# USBBreakout-2_0.net
KiCad netlist of a schematic drawn in EAGLE
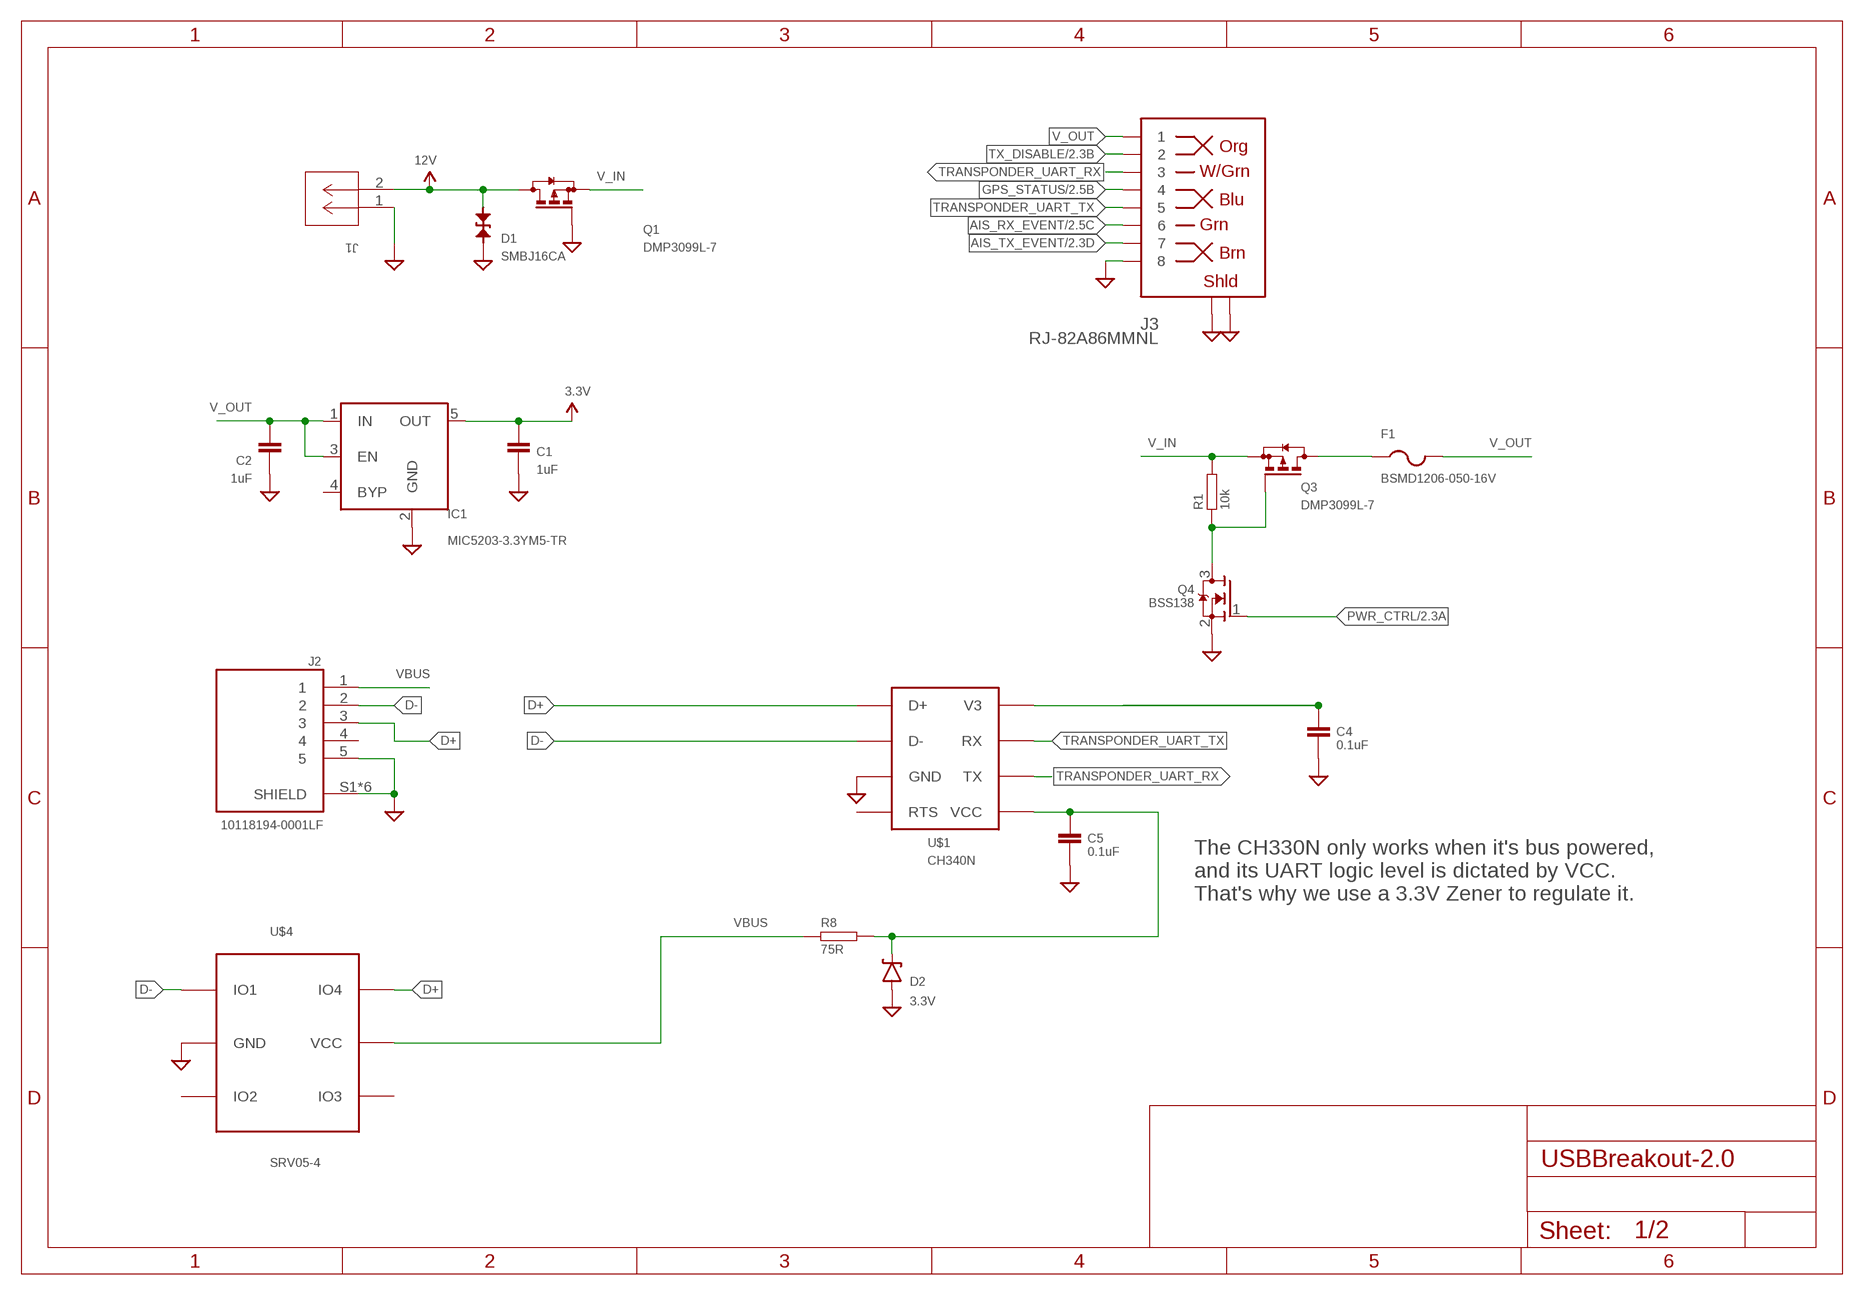
[diagram p0: schematic, sheet 1]
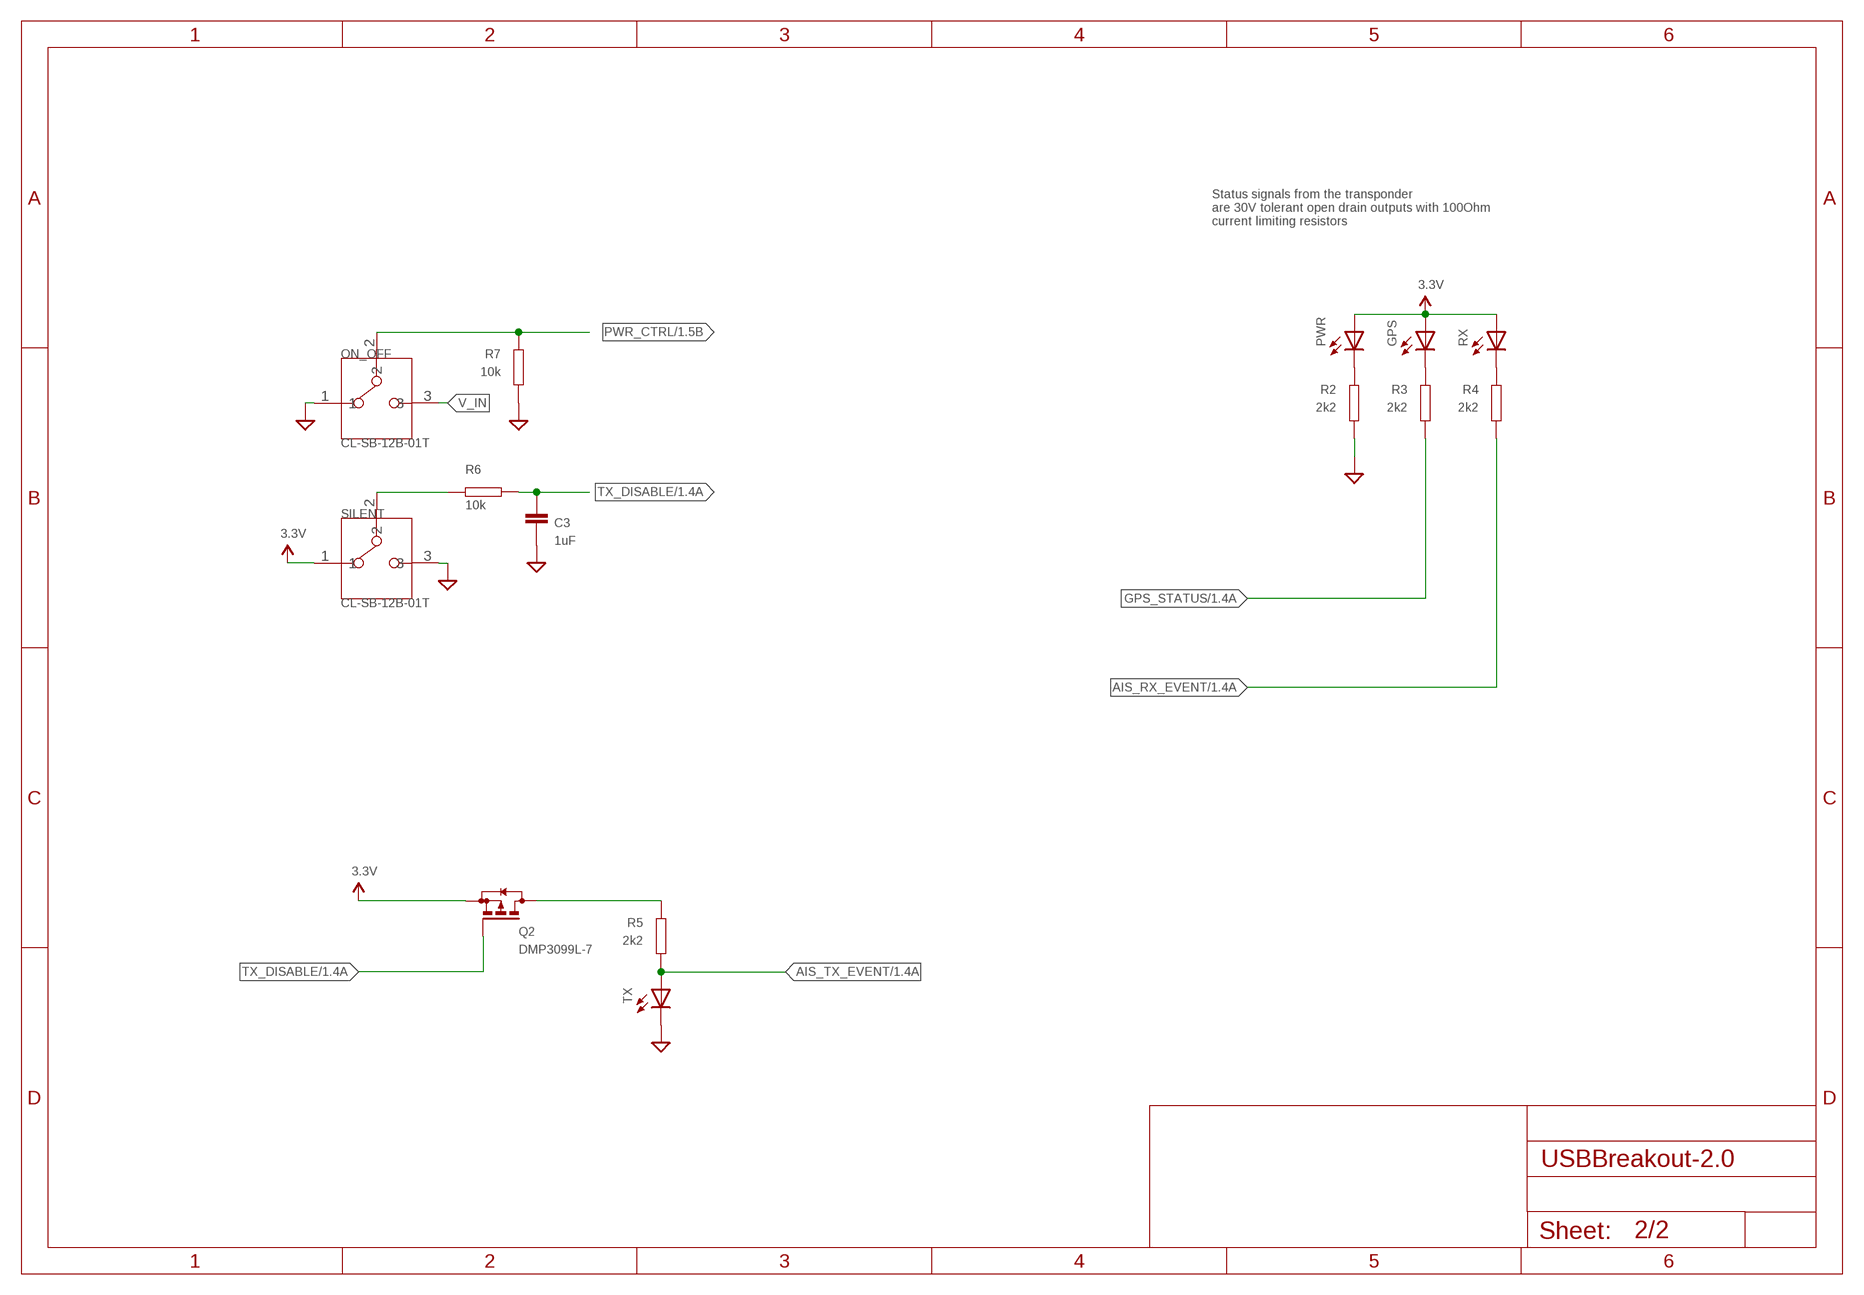
[diagram p1: schematic, sheet 2]

(export (version "E")
  (design (tool "Eeschema 10.0.6"))
  (components
    (comp (ref "C1")
      (value "1uF")
      (footprint "eagle-import:0603")
      (libsource (lib "eagle-import") (part "CAPACITOR0603"))
    )
    (comp (ref "C2")
      (value "1uF")
      (footprint "eagle-import:0603")
      (libsource (lib "eagle-import") (part "CAPACITOR0603"))
    )
    (comp (ref "C4")
      (value "0.1uF")
      (footprint "eagle-import:0603")
      (libsource (lib "eagle-import") (part "CAPACITOR0603"))
    )
    (comp (ref "C5")
      (value "0.1uF")
      (footprint "eagle-import:0603")
      (libsource (lib "eagle-import") (part "CAPACITOR0603"))
    )
    (comp (ref "D1")
      (value "SMBJ16CA")
      (footprint "eagle-import:SMB-BIDIR")
      (libsource (lib "eagle-import") (part "DIODE-TVS-BIDIRSMB"))
    )
    (comp (ref "D2")
      (value "3.3V")
      (footprint "eagle-import:SOD-323")
      (libsource (lib "eagle-import") (part "DIODE-ZENER3.3V"))
    )
    (comp (ref "F1")
      (value "BSMD1206-050-16V")
      (footprint "eagle-import:R1206")
      (libsource (lib "eagle-import") (part "PTCFUSE-1206"))
    )
    (comp (ref "IC1")
      (value "MIC5203-3.3YM5-TR")
      (footprint "eagle-import:SOT23-5")
      (libsource (lib "eagle-import") (part "MIC5219XX"))
    )
    (comp (ref "J1")
      (value "OSTVN02A150")
      (footprint "eagle-import:CONN_OSTVN02A150_OST")
      (fields (field (name "COPYRIGHT") "Copyright (C) 2018 Accelerated Designs. All rights reserved"))
      (libsource (lib "eagle-import") (part "OSTVN02A150"))
    )
    (comp (ref "J2")
      (value "10118194-0001LF")
      (footprint "eagle-import:AMPHENOL_10118194-0001LF")
      (fields (field (name "MF") "Amphenol ICC (FCI)"))
      (libsource (lib "eagle-import") (part "10118194-0001LF"))
    )
    (comp (ref "J3")
      (value "RJ-82A86MMNL")
      (footprint "eagle-import:RJ-82A86MMNL")
      (libsource (lib "eagle-import") (part "RJ-82A86MMNL"))
    )
    (comp (ref "Q1")
      (value "DMP3099L-7")
      (footprint "eagle-import:SOT23")
      (libsource (lib "eagle-import") (part "BSS84"))
    )
    (comp (ref "Q3")
      (value "DMP3099L-7")
      (footprint "eagle-import:SOT23")
      (libsource (lib "eagle-import") (part "BSS84"))
    )
    (comp (ref "Q4")
      (value "BSS138")
      (footprint "eagle-import:SOT23")
      (libsource (lib "eagle-import") (part "MOSFET-NREFLOW"))
    )
    (comp (ref "R1")
      (value "10k")
      (footprint "eagle-import:0603")
      (libsource (lib "eagle-import") (part "RESISTOR0603"))
    )
    (comp (ref "R8")
      (value "75R")
      (footprint "eagle-import:0603")
      (libsource (lib "eagle-import") (part "RESISTOR0603"))
    )
    (comp (ref "U$1")
      (value "CH340N")
      (footprint "eagle-import:SOIC-8")
      (libsource (lib "eagle-import") (part "CH330N"))
    )
    (comp (ref "U$4")
      (value "SRV05-4")
      (footprint "eagle-import:SOT23-6")
      (libsource (lib "eagle-import") (part "SRV05-4"))
    )
    (comp (ref "C3")
      (value "1uF")
      (footprint "eagle-import:0603")
      (libsource (lib "eagle-import") (part "CAPACITOR0603"))
    )
    (comp (ref "GPS")
      (value "LEDCHIPLED_1206")
      (footprint "eagle-import:CHIPLED_1206")
      (fields (field (name "PARTNO") "TJ-S3216CL9T5ALC2G-A5"))
      (libsource (lib "eagle-import") (part "LEDCHIPLED_1206"))
    )
    (comp (ref "ON_OFF")
      (value "CL-SB-12B-01T")
      (footprint "eagle-import:CL-SB-12B")
      (fields (field (name "MF") "Nidec Copal"))
      (libsource (lib "eagle-import") (part "CL-SB-12B-01T"))
    )
    (comp (ref "PWR")
      (value "LEDCHIPLED_1206")
      (footprint "eagle-import:CHIPLED_1206")
      (fields (field (name "PARTNO") "TJ-S3216CL9T5ALC2G-A5"))
      (libsource (lib "eagle-import") (part "LEDCHIPLED_1206"))
    )
    (comp (ref "Q2")
      (value "DMP3099L-7")
      (footprint "eagle-import:SOT23")
      (libsource (lib "eagle-import") (part "BSS84"))
    )
    (comp (ref "R2")
      (value "2k2")
      (footprint "eagle-import:0603")
      (libsource (lib "eagle-import") (part "RESISTOR0603"))
    )
    (comp (ref "R3")
      (value "2k2")
      (footprint "eagle-import:0603")
      (libsource (lib "eagle-import") (part "RESISTOR0603"))
    )
    (comp (ref "R4")
      (value "2k2")
      (footprint "eagle-import:0603")
      (libsource (lib "eagle-import") (part "RESISTOR0603"))
    )
    (comp (ref "R5")
      (value "2k2")
      (footprint "eagle-import:0603")
      (libsource (lib "eagle-import") (part "RESISTOR0603"))
    )
    (comp (ref "R6")
      (value "10k")
      (footprint "eagle-import:0603")
      (libsource (lib "eagle-import") (part "RESISTOR0603"))
    )
    (comp (ref "R7")
      (value "10k")
      (footprint "eagle-import:0603")
      (libsource (lib "eagle-import") (part "RESISTOR0603"))
    )
    (comp (ref "RX")
      (value "LEDCHIPLED_1206")
      (footprint "eagle-import:CHIPLED_1206")
      (fields (field (name "PARTNO") "TJ-S3216CL9T5ALC2G-A5"))
      (libsource (lib "eagle-import") (part "LEDCHIPLED_1206"))
    )
    (comp (ref "SILENT")
      (value "CL-SB-12B-01T")
      (footprint "eagle-import:CL-SB-12B")
      (fields (field (name "MF") "Nidec Copal"))
      (libsource (lib "eagle-import") (part "CL-SB-12B-01T"))
    )
    (comp (ref "TX")
      (value "LEDCHIPLED_1206")
      (footprint "eagle-import:CHIPLED_1206")
      (fields (field (name "PARTNO") "TJ-S3216CL9T5ALC2G-A5"))
      (libsource (lib "eagle-import") (part "LEDCHIPLED_1206"))
    )
  )
  (nets
    (net (code "1") (name "3.3V") (class "Default")
      (node (ref "C1") (pin "P$1") (pinfunction "1_P$1") (pintype "passive"))
      (node (ref "GPS") (pin "A") (pinfunction "A_A") (pintype "passive"))
      (node (ref "IC1") (pin "5") (pinfunction "OUT_5") (pintype "output"))
      (node (ref "PWR") (pin "A") (pinfunction "A_A") (pintype "passive"))
      (node (ref "Q2") (pin "2") (pinfunction "S_2") (pintype "passive"))
      (node (ref "RX") (pin "A") (pinfunction "A_A") (pintype "passive"))
      (node (ref "SILENT") (pin "1") (pinfunction "1_1") (pintype "bidirectional"))
    )
    (net (code "2") (name "12V") (class "Default")
      (node (ref "D1") (pin "A") (pinfunction "P$1_A") (pintype "bidirectional"))
      (node (ref "J1") (pin "2") (pinfunction "2_2") (pintype "passive"))
      (node (ref "Q1") (pin "3") (pinfunction "D_3") (pintype "passive"))
    )
    (net (code "3") (name "AIS_RX_EVENT") (class "Default")
      (node (ref "J3") (pin "P$6") (pinfunction "6_P$6") (pintype "bidirectional"))
      (node (ref "R4") (pin "P$2") (pinfunction "P$2_P$2") (pintype "passive"))
    )
    (net (code "4") (name "AIS_TX_EVENT") (class "Default")
      (node (ref "J3") (pin "P$7") (pinfunction "7_P$7") (pintype "bidirectional"))
      (node (ref "R5") (pin "P$2") (pinfunction "P$2_P$2") (pintype "passive"))
      (node (ref "TX") (pin "A") (pinfunction "A_A") (pintype "passive"))
    )
    (net (code "5") (name "D+") (class "Default")
      (node (ref "J2") (pin "3") (pinfunction "3_3") (pintype "passive"))
      (node (ref "U$1") (pin "1") (pinfunction "D+_1") (pintype "bidirectional"))
      (node (ref "U$4") (pin "6") (pinfunction "IO4_6") (pintype "bidirectional"))
    )
    (net (code "6") (name "D-") (class "Default")
      (node (ref "J2") (pin "2") (pinfunction "2_2") (pintype "passive"))
      (node (ref "U$1") (pin "2") (pinfunction "D-_2") (pintype "bidirectional"))
      (node (ref "U$4") (pin "1") (pinfunction "IO1_1") (pintype "bidirectional"))
    )
    (net (code "7") (name "GND") (class "Default")
      (node (ref "C1") (pin "P$2") (pinfunction "2_P$2") (pintype "passive"))
      (node (ref "C2") (pin "P$2") (pinfunction "2_P$2") (pintype "passive"))
      (node (ref "C3") (pin "P$2") (pinfunction "2_P$2") (pintype "passive"))
      (node (ref "C4") (pin "P$2") (pinfunction "2_P$2") (pintype "passive"))
      (node (ref "C5") (pin "P$2") (pinfunction "2_P$2") (pintype "passive"))
      (node (ref "D1") (pin "C") (pinfunction "P$2_C") (pintype "bidirectional"))
      (node (ref "D2") (pin "A") (pinfunction "A_A") (pintype "passive"))
      (node (ref "IC1") (pin "2") (pinfunction "GND_2") (pintype "power_in"))
      (node (ref "J1") (pin "1") (pinfunction "1_1") (pintype "passive"))
      (node (ref "J2") (pin "5") (pinfunction "5_5") (pintype "passive"))
      (node (ref "J2") (pin "S1") (pinfunction "SHIELD_S1") (pintype "passive"))
      (node (ref "J2") (pin "S2") (pinfunction "SHIELD_S2") (pintype "passive"))
      (node (ref "J2") (pin "S3") (pinfunction "SHIELD_S3") (pintype "passive"))
      (node (ref "J2") (pin "S4") (pinfunction "SHIELD_S4") (pintype "passive"))
      (node (ref "J2") (pin "S5") (pinfunction "SHIELD_S5") (pintype "passive"))
      (node (ref "J2") (pin "S6") (pinfunction "SHIELD_S6") (pintype "passive"))
      (node (ref "J3") (pin "P$10") (pinfunction "SHLD_P$10") (pintype "bidirectional"))
      (node (ref "J3") (pin "P$11") (pinfunction "SHLD_P$11") (pintype "bidirectional"))
      (node (ref "J3") (pin "P$12") (pinfunction "SHLD_P$12") (pintype "bidirectional"))
      (node (ref "J3") (pin "P$8") (pinfunction "8_P$8") (pintype "bidirectional"))
      (node (ref "J3") (pin "P$9") (pinfunction "SHLD_P$9") (pintype "bidirectional"))
      (node (ref "ON_OFF") (pin "1") (pinfunction "1_1") (pintype "bidirectional"))
      (node (ref "Q1") (pin "1") (pinfunction "G_1") (pintype "passive"))
      (node (ref "Q4") (pin "2") (pinfunction "S_2") (pintype "bidirectional"))
      (node (ref "R2") (pin "P$2") (pinfunction "P$2_P$2") (pintype "passive"))
      (node (ref "R7") (pin "P$2") (pinfunction "P$2_P$2") (pintype "passive"))
      (node (ref "SILENT") (pin "3") (pinfunction "3_3") (pintype "bidirectional"))
      (node (ref "TX") (pin "C") (pinfunction "C_C") (pintype "passive"))
      (node (ref "U$1") (pin "3") (pinfunction "GND_3") (pintype "bidirectional"))
      (node (ref "U$4") (pin "2") (pinfunction "GND_2") (pintype "bidirectional"))
    )
    (net (code "8") (name "GPS_STATUS") (class "Default")
      (node (ref "J3") (pin "P$4") (pinfunction "4_P$4") (pintype "bidirectional"))
      (node (ref "R3") (pin "P$2") (pinfunction "P$2_P$2") (pintype "passive"))
    )
    (net (code "9") (name "Net-(C4-1)") (class "Default")
      (node (ref "C4") (pin "P$1") (pinfunction "1_P$1") (pintype "passive"))
      (node (ref "U$1") (pin "8") (pinfunction "V3_8") (pintype "bidirectional"))
    )
    (net (code "10") (name "Net-(C5-1)") (class "Default")
      (node (ref "C5") (pin "P$1") (pinfunction "1_P$1") (pintype "passive"))
      (node (ref "D2") (pin "C") (pinfunction "C_C") (pintype "passive"))
      (node (ref "R8") (pin "P$2") (pinfunction "P$2_P$2") (pintype "passive"))
      (node (ref "U$1") (pin "5") (pinfunction "VCC_5") (pintype "bidirectional"))
    )
    (net (code "11") (name "Net-(GPS-PadC)") (class "Default")
      (node (ref "GPS") (pin "C") (pinfunction "C_C") (pintype "passive"))
      (node (ref "R3") (pin "P$1") (pinfunction "P$1_P$1") (pintype "passive"))
    )
    (net (code "12") (name "Net-(PWR-PadC)") (class "Default")
      (node (ref "PWR") (pin "C") (pinfunction "C_C") (pintype "passive"))
      (node (ref "R2") (pin "P$1") (pinfunction "P$1_P$1") (pintype "passive"))
    )
    (net (code "13") (name "Net-(Q2-D)") (class "Default")
      (node (ref "Q2") (pin "3") (pinfunction "D_3") (pintype "passive"))
      (node (ref "R5") (pin "P$1") (pinfunction "P$1_P$1") (pintype "passive"))
    )
    (net (code "14") (name "Net-(Q3-D)") (class "Default")
      (node (ref "F1") (pin "1") (pinfunction "1_1") (pintype "passive"))
      (node (ref "Q3") (pin "3") (pinfunction "D_3") (pintype "passive"))
    )
    (net (code "15") (name "Net-(Q3-G)") (class "Default")
      (node (ref "Q3") (pin "1") (pinfunction "G_1") (pintype "passive"))
      (node (ref "Q4") (pin "3") (pinfunction "D_3") (pintype "bidirectional"))
      (node (ref "R1") (pin "P$1") (pinfunction "P$1_P$1") (pintype "passive"))
    )
    (net (code "16") (name "Net-(R4-PadP$1)") (class "Default")
      (node (ref "R4") (pin "P$1") (pinfunction "P$1_P$1") (pintype "passive"))
      (node (ref "RX") (pin "C") (pinfunction "C_C") (pintype "passive"))
    )
    (net (code "17") (name "Net-(R6-PadP$1)") (class "Default")
      (node (ref "R6") (pin "P$1") (pinfunction "P$1_P$1") (pintype "passive"))
      (node (ref "SILENT") (pin "2") (pinfunction "2_2") (pintype "bidirectional"))
    )
    (net (code "18") (name "PWR_CTRL") (class "Default")
      (node (ref "ON_OFF") (pin "2") (pinfunction "2_2") (pintype "bidirectional"))
      (node (ref "Q4") (pin "1") (pinfunction "G_1") (pintype "bidirectional"))
      (node (ref "R7") (pin "P$1") (pinfunction "P$1_P$1") (pintype "passive"))
    )
    (net (code "19") (name "TRANSPONDER_UART_RX") (class "Default")
      (node (ref "J3") (pin "P$3") (pinfunction "3_P$3") (pintype "bidirectional"))
      (node (ref "U$1") (pin "6") (pinfunction "TX_6") (pintype "bidirectional"))
    )
    (net (code "20") (name "TRANSPONDER_UART_TX") (class "Default")
      (node (ref "J3") (pin "P$5") (pinfunction "5_P$5") (pintype "bidirectional"))
      (node (ref "U$1") (pin "7") (pinfunction "RX_7") (pintype "bidirectional"))
    )
    (net (code "21") (name "TX_DISABLE") (class "Default")
      (node (ref "C3") (pin "P$1") (pinfunction "1_P$1") (pintype "passive"))
      (node (ref "J3") (pin "P$2") (pinfunction "2_P$2") (pintype "bidirectional"))
      (node (ref "Q2") (pin "1") (pinfunction "G_1") (pintype "passive"))
      (node (ref "R6") (pin "P$2") (pinfunction "P$2_P$2") (pintype "passive"))
    )
    (net (code "22") (name "VBUS") (class "Default")
      (node (ref "J2") (pin "1") (pinfunction "1_1") (pintype "passive"))
      (node (ref "R8") (pin "P$1") (pinfunction "P$1_P$1") (pintype "passive"))
      (node (ref "U$4") (pin "5") (pinfunction "VCC_5") (pintype "bidirectional"))
    )
    (net (code "23") (name "V_IN") (class "Default")
      (node (ref "ON_OFF") (pin "3") (pinfunction "3_3") (pintype "bidirectional"))
      (node (ref "Q1") (pin "2") (pinfunction "S_2") (pintype "passive"))
      (node (ref "Q3") (pin "2") (pinfunction "S_2") (pintype "passive"))
      (node (ref "R1") (pin "P$2") (pinfunction "P$2_P$2") (pintype "passive"))
    )
    (net (code "24") (name "V_OUT") (class "Default")
      (node (ref "C2") (pin "P$1") (pinfunction "1_P$1") (pintype "passive"))
      (node (ref "F1") (pin "2") (pinfunction "2_2") (pintype "passive"))
      (node (ref "IC1") (pin "1") (pinfunction "IN_1") (pintype "input"))
      (node (ref "IC1") (pin "3") (pinfunction "EN_3") (pintype "input"))
      (node (ref "J3") (pin "P$1") (pinfunction "1_P$1") (pintype "bidirectional"))
    )
    (net (code "25") (name "unconnected-(IC1-BYP-Pad4)") (class "Default")
      (node (ref "IC1") (pin "4") (pinfunction "BYP_4") (pintype "passive"))
    )
    (net (code "26") (name "unconnected-(J2-Pad4)") (class "Default")
      (node (ref "J2") (pin "4") (pinfunction "4_4") (pintype "passive"))
    )
    (net (code "27") (name "unconnected-(U$1-RTS-Pad4)") (class "Default")
      (node (ref "U$1") (pin "4") (pinfunction "RTS_4") (pintype "bidirectional"))
    )
    (net (code "28") (name "unconnected-(U$4-IO2-Pad3)") (class "Default")
      (node (ref "U$4") (pin "3") (pinfunction "IO2_3") (pintype "bidirectional"))
    )
    (net (code "29") (name "unconnected-(U$4-IO3-Pad4)") (class "Default")
      (node (ref "U$4") (pin "4") (pinfunction "IO3_4") (pintype "bidirectional"))
    )
  )
)
